# Mikrolysreklamen.net
KiCad netlist of a schematic drawn in Altium Designer
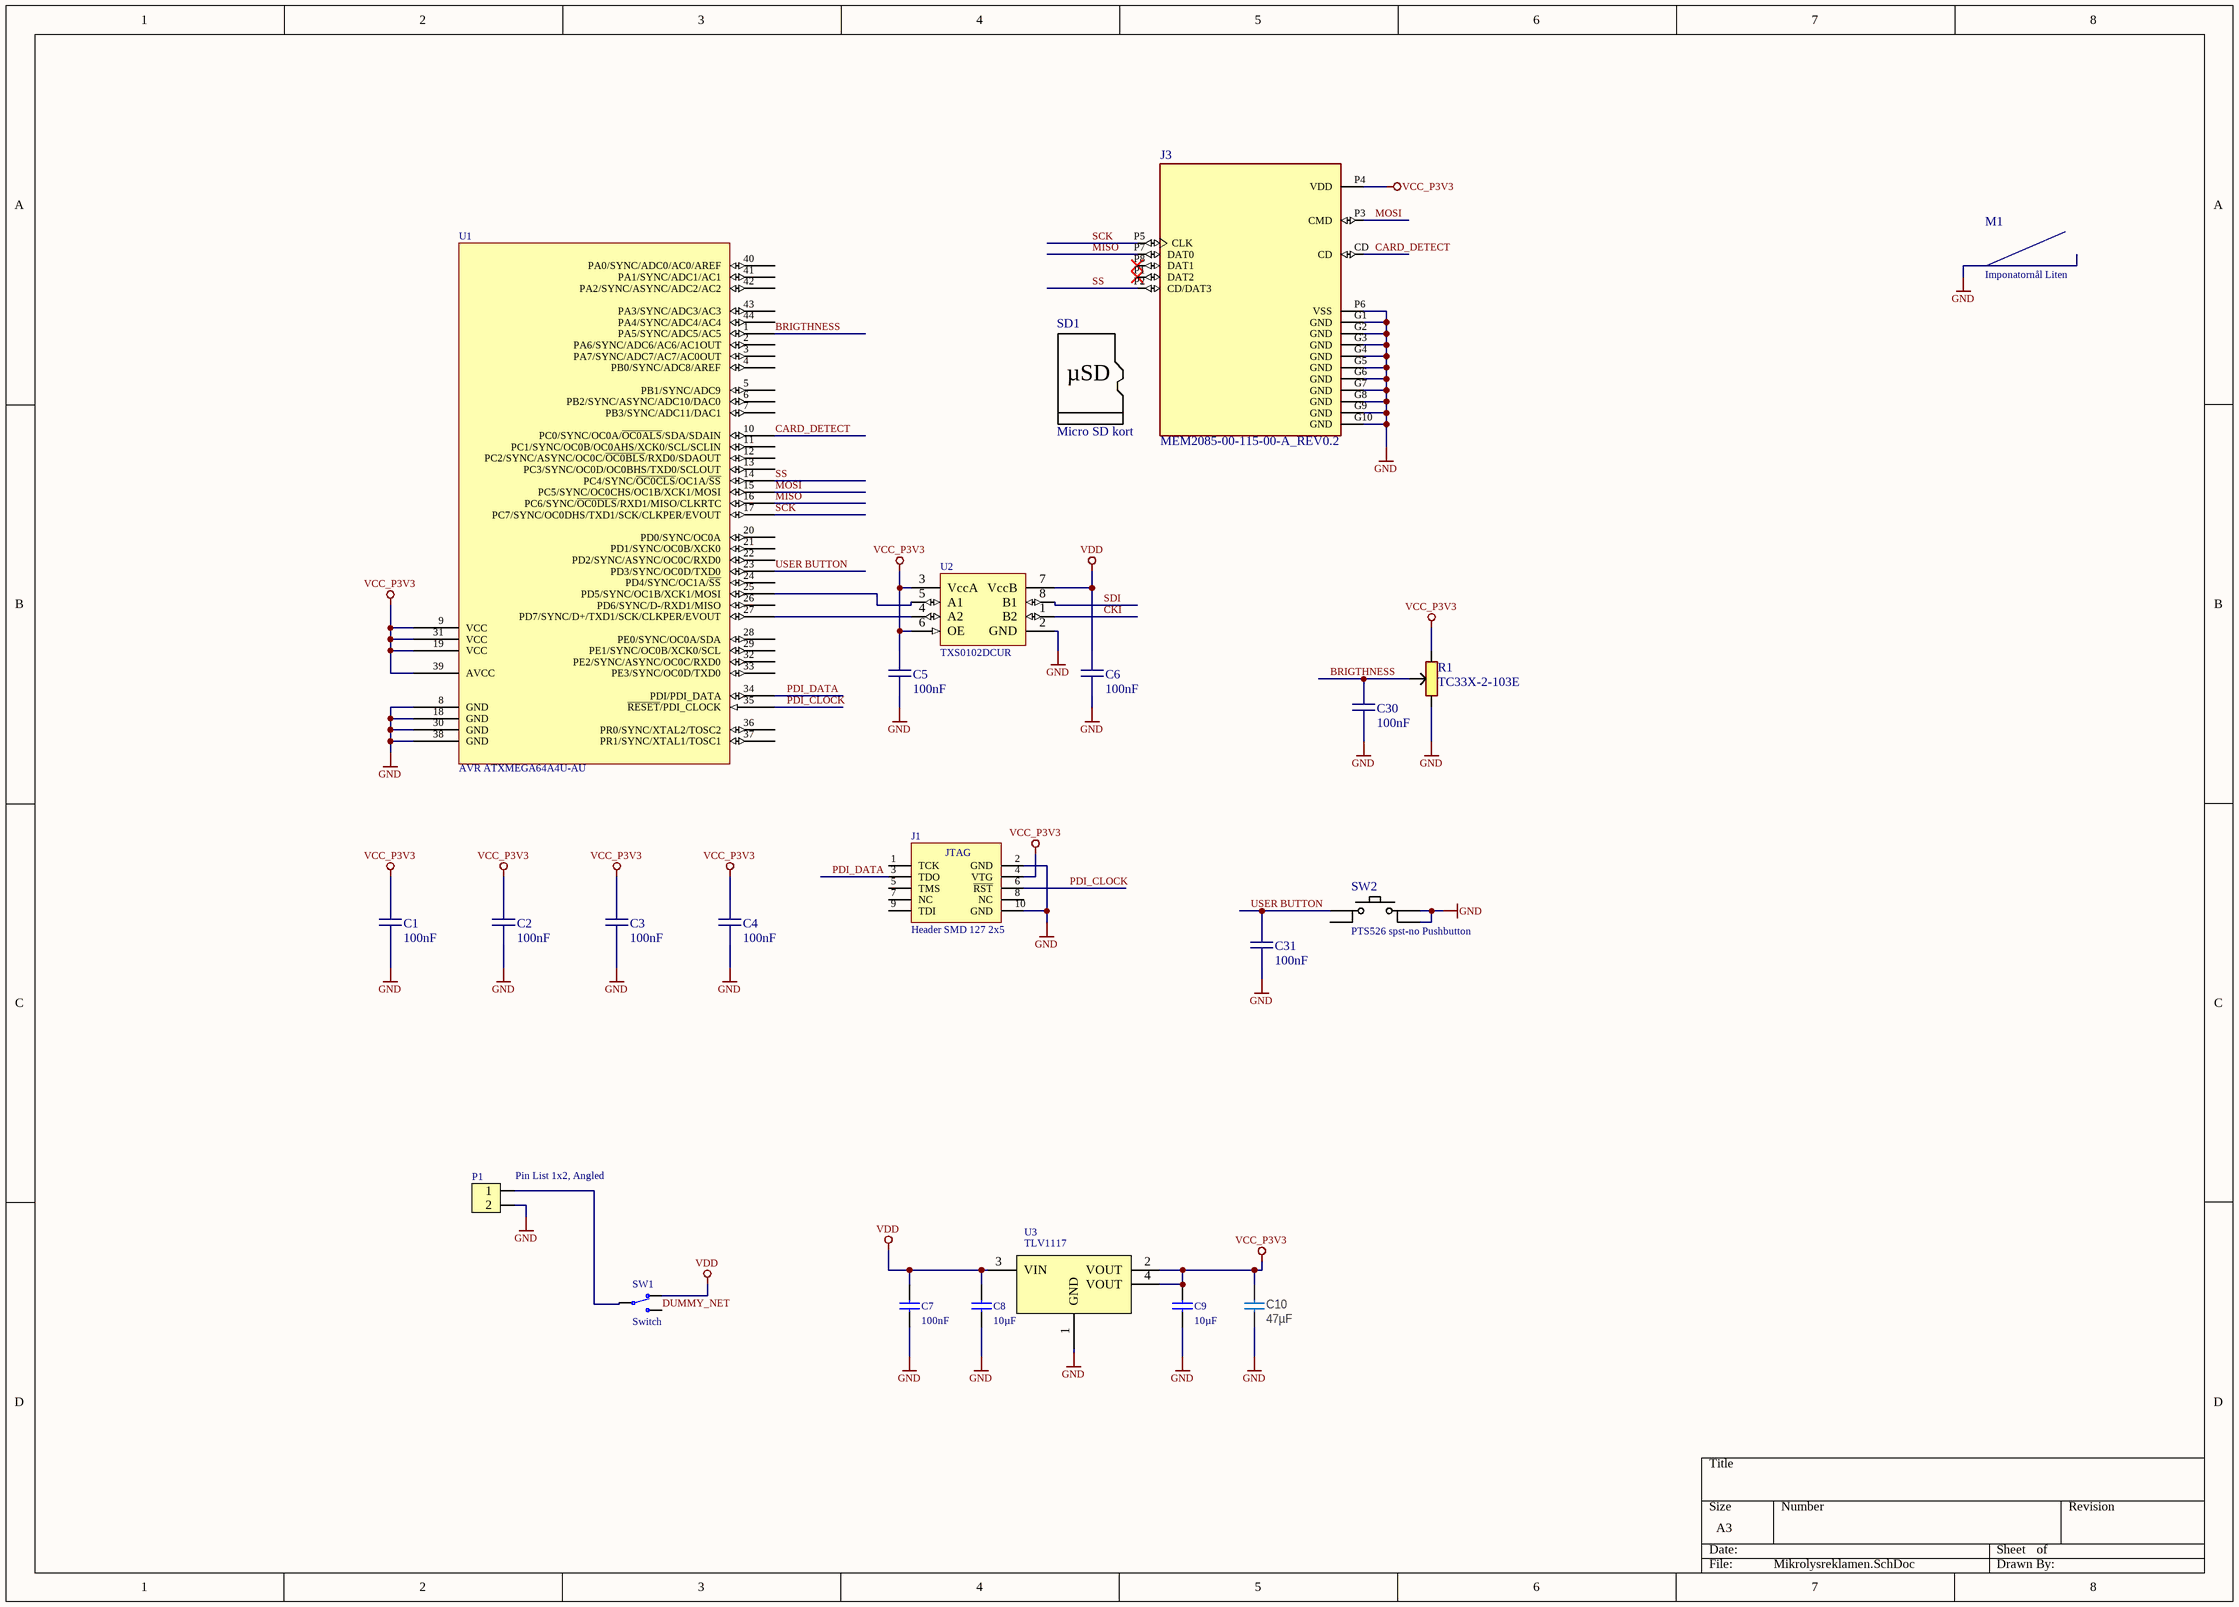
[diagram p0: Mikrolysreklamen.SchDoc]

(export (version "E")
  (design (tool "Eeschema 10.0.6"))
  (components
    (comp (ref "C1")
      (value "100nF")
      (footprint "CAPC0603(1608)55_N")
      (libsource (lib "OVLib_64") (part "CAP"))
    )
    (comp (ref "C2")
      (value "100nF")
      (footprint "CAPC0603(1608)55_N")
      (libsource (lib "OVLib_64") (part "CAP"))
    )
    (comp (ref "C3")
      (value "100nF")
      (footprint "CAPC0603(1608)55_N")
      (libsource (lib "OVLib_64") (part "CAP"))
    )
    (comp (ref "C4")
      (value "100nF")
      (footprint "CAPC0603(1608)55_N")
      (libsource (lib "OVLib_64") (part "CAP"))
    )
    (comp (ref "C5")
      (value "100nF")
      (footprint "CAPC0603(1608)55_N")
      (libsource (lib "OVLib_64") (part "CAP"))
    )
    (comp (ref "C6")
      (value "100nF")
      (footprint "CAPC0603(1608)55_N")
      (libsource (lib "OVLib_64") (part "CAP"))
    )
    (comp (ref "C7")
      (value "100nF")
      (footprint "CAPC1005X04L")
      (description "Capacitor, X7R, ±10%")
      (fields (field (name "PART NUMBER") "C0402-100n") (field (name "PUBLISHER") "Nordic Semiconductor"))
      (libsource (lib "Nordic Passive DB") (part "CAP"))
    )
    (comp (ref "C8")
      (value "10µF")
      (footprint "CAPC1608X06L")
      (description "Capacitor, X5R, ±20%")
      (fields (field (name "PART NUMBER") "C0603-10µ") (field (name "PUBLISHER") "Nordic Semiconductor"))
      (libsource (lib "Nordic Passive DB") (part "CAP"))
    )
    (comp (ref "C9")
      (value "10µF")
      (footprint "CAPC1608X06L")
      (description "Capacitor, X5R, ±20%")
      (fields (field (name "PART NUMBER") "C0603-10µ") (field (name "PUBLISHER") "Nordic Semiconductor"))
      (libsource (lib "Nordic Passive DB") (part "CAP"))
    )
    (comp (ref "C10")
      (value "47µF")
      (footprint "CAPC2012X11L")
      (description "Capacitor, X5R, ±20%, 6.3V")
      (fields
        (field (name "PART NUMBER") "C0805-47µ")
        (field (name "MANUFACTURER") "Taiyo Yuden")
        (field (name "PUBLISHER") "Nordic Semiconductor")
      )
      (libsource (lib "Nordic Passive DB") (part "CAP"))
    )
    (comp (ref "C30")
      (value "100nF")
      (footprint "CAPC0603(1608)55_N")
      (libsource (lib "OVLib_64") (part "CAP"))
    )
    (comp (ref "C31")
      (value "100nF")
      (footprint "CAPC0603(1608)55_N")
      (libsource (lib "OVLib_64") (part "CAP"))
    )
    (comp (ref "J1")
      (value "Header SMD 127 2x5")
      (footprint "SMDHDRV10P127_2X5_615X330X560B")
      (description "1,27mm Pitch SMD Header")
      (libsource (lib "OVLib") (part "AVRJTAG"))
    )
    (comp (ref "J3")
      (value "MEM2085-00-115-00-A_REV0.2")
      (footprint "GCT_MEM2085-00-115-00-A_REV0.2")
      (description "MicroSD Push pull Memory Card Connector")
      (fields (field (name "MP") "MEM2085-00-115-00-A") (field (name "MF") "Global Connector Technology"))
      (libsource (lib "OVLib_64") (part "MEM2085-00-115-00-A_REV0.2"))
    )
    (comp (ref "M1")
      (value "Imponatornål Liten")
      (footprint "Imponatornaal_liten")
      (libsource (lib "Imponatornaal") (part "Imponatornaal"))
    )
    (comp (ref "P1")
      (value "Pin List 1x2, Angled")
      (footprint "LIST_ANG_1x2-SMD-2.54MM")
      (description "Pin List 1x2, 2.54mm (100mil), Right Angled, SMD")
      (fields
        (field (name "PART NUMBER") "Pin List Ang 1x2 SMD, 2.54mm")
        (field (name "MANUFACTURER") "W-CON")
        (field (name "PUBLISHER") "Nordic Semiconductor")
      )
      (libsource (lib "Nordic Passive DB") (part "CONN-2"))
    )
    (comp (ref "R1")
      (value "TC33X-2-103E")
      (footprint "TRIM_TC33X-2-103E")
      (libsource (lib "OVLib_64") (part "Potmeter"))
    )
    (comp (ref "SD1")
      (value "Micro SD kort")
      (footprint "microsdcard")
      (libsource (lib "OVLib_64") (part "microsdcard"))
    )
    (comp (ref "SW1")
      (value "Switch")
      (footprint "JS102011SAQN")
      (description "SMD slide Switch (ON-ON)")
      (fields
        (field (name "PART NUMBER") "JS102011SAQN")
        (field (name "MANUFACTURER") "C&K Components")
        (field (name "PUBLISHER") "Nordic Semiconductor")
      )
      (libsource (lib "Nordic Discrete DB") (part "SW-SPDT"))
    )
    (comp (ref "SW2")
      (value "PTS526 spst-no Pushbutton")
      (footprint "PTS526_SK15_SMTR2_LFS")
      (libsource (lib "OVLib_64") (part "Pushbutton"))
    )
    (comp (ref "U1")
      (value "AVR ATXMEGA64A4U-AU")
      (footprint "TQFP80P1200X1200X120-44N")
      (description "Mikrokontroller")
      (libsource (lib "OVLib") (part "ATXMEGA-A4U"))
    )
    (comp (ref "U2")
      (value "TXS0102DCUR")
      (footprint "TSSOP50P310X90-8N")
      (description "IC VOLT-LEVEL TRANSLATOR 8-US8")
      (fields
        (field (name "MANUFACTURER") "Texas Instruments")
        (field (name "PUBLISHER") "Nordic Semiconductor")
      )
      (libsource (lib "Nordic Active DB") (part "TXS0102DC"))
    )
    (comp (ref "U3")
      (value "TLV1117")
      (footprint "SOT230P700X180-4N")
      (description "REG LDO 3.3V 0.8A SOT223")
      (fields
        (field (name "PART NUMBER") "TLV1117-33CDCYR")
        (field (name "MANUFACTURER") "Texas Instruments")
        (field (name "PUBLISHER") "Nordic Semiconductor")
      )
      (libsource (lib "Nordic Active DB") (part "LD1117_fixed"))
    )
  )
  (nets
    (net (code "1") (name "/BRIGTHNESS") (class "Default")
      (node (ref "C30") (pin "2") (pinfunction "2_2") (pintype "passive"))
      (node (ref "R1") (pin "2") (pinfunction "2_2") (pintype "passive"))
      (node (ref "U1") (pin "1") (pinfunction "PA5/SYNC/ADC5/AC5_1") (pintype "bidirectional"))
    )
    (net (code "2") (name "/CARD_DETECT") (class "Default")
      (node (ref "J3") (pin "CD") (pinfunction "CD_CD") (pintype "bidirectional"))
      (node (ref "U1") (pin "10") (pinfunction "PC0/SYNC/OC0A/~{OC0ALS}/SDA/SDAIN_10") (pintype "bidirectional"))
    )
    (net (code "3") (name "/CKI") (class "Default")
      (node (ref "U2") (pin "1") (pinfunction "B2_1") (pintype "bidirectional"))
    )
    (net (code "4") (name "/DUMMY_NET") (class "Default")
      (node (ref "SW1") (pin "3") (pinfunction "N.O_3") (pintype "passive"))
    )
    (net (code "5") (name "/MISO") (class "Default")
      (node (ref "J3") (pin "P7") (pinfunction "DAT0_P7") (pintype "bidirectional"))
      (node (ref "U1") (pin "16") (pinfunction "PC6/SYNC/~{OC0DLS}/RXD1/MISO/CLKRTC_16") (pintype "bidirectional"))
    )
    (net (code "6") (name "/MOSI") (class "Default")
      (node (ref "J3") (pin "P3") (pinfunction "CMD_P3") (pintype "bidirectional"))
      (node (ref "U1") (pin "15") (pinfunction "PC5/SYNC/OC0CHS/OC1B/XCK1/MOSI_15") (pintype "bidirectional"))
    )
    (net (code "7") (name "/PDI_CLOCK") (class "Default")
      (node (ref "J1") (pin "6") (pinfunction "~{RST}_6") (pintype "passive"))
      (node (ref "U1") (pin "35") (pinfunction "~{RESET}/PDI_CLOCK_35") (pintype "input"))
    )
    (net (code "8") (name "/PDI_DATA") (class "Default")
      (node (ref "J1") (pin "3") (pinfunction "TDO_3") (pintype "passive"))
      (node (ref "U1") (pin "34") (pinfunction "PDI/PDI_DATA_34") (pintype "bidirectional"))
    )
    (net (code "9") (name "/SCK") (class "Default")
      (node (ref "J3") (pin "P5") (pinfunction "CLK_P5") (pintype "bidirectional"))
      (node (ref "U1") (pin "17") (pinfunction "PC7/SYNC/OC0DHS/TXD1/SCK/CLKPER/EVOUT_17") (pintype "bidirectional"))
    )
    (net (code "10") (name "/SDI") (class "Default")
      (node (ref "U2") (pin "8") (pinfunction "B1_8") (pintype "bidirectional"))
    )
    (net (code "11") (name "/SS") (class "Default")
      (node (ref "J3") (pin "P2") (pinfunction "CD/DAT3_P2") (pintype "bidirectional"))
      (node (ref "U1") (pin "14") (pinfunction "PC4/SYNC/~{OC0CLS}/OC1A/~{SS}_14") (pintype "bidirectional"))
    )
    (net (code "12") (name "/USER BUTTON") (class "Default")
      (node (ref "C31") (pin "2") (pinfunction "2_2") (pintype "passive"))
      (node (ref "SW2") (pin "1") (pinfunction "1_1") (pintype "passive"))
      (node (ref "U1") (pin "23") (pinfunction "PD3/SYNC/OC0D/TXD0_23") (pintype "bidirectional"))
    )
    (net (code "13") (name "GND") (class "Default")
      (node (ref "C1") (pin "1") (pinfunction "1_1") (pintype "passive"))
      (node (ref "C10") (pin "1") (pinfunction "1_1") (pintype "passive"))
      (node (ref "C2") (pin "1") (pinfunction "1_1") (pintype "passive"))
      (node (ref "C3") (pin "1") (pinfunction "1_1") (pintype "passive"))
      (node (ref "C30") (pin "1") (pinfunction "1_1") (pintype "passive"))
      (node (ref "C31") (pin "1") (pinfunction "1_1") (pintype "passive"))
      (node (ref "C4") (pin "1") (pinfunction "1_1") (pintype "passive"))
      (node (ref "C5") (pin "1") (pinfunction "1_1") (pintype "passive"))
      (node (ref "C6") (pin "1") (pinfunction "1_1") (pintype "passive"))
      (node (ref "C7") (pin "1") (pinfunction "1_1") (pintype "passive"))
      (node (ref "C8") (pin "1") (pinfunction "1_1") (pintype "passive"))
      (node (ref "C9") (pin "1") (pinfunction "1_1") (pintype "passive"))
      (node (ref "J1") (pin "10") (pinfunction "GND_10") (pintype "passive"))
      (node (ref "J1") (pin "2") (pinfunction "GND_2") (pintype "passive"))
      (node (ref "J3") (pin "G1") (pinfunction "GND_G1") (pintype "power_in"))
      (node (ref "J3") (pin "G10") (pinfunction "GND_G10") (pintype "power_in"))
      (node (ref "J3") (pin "G2") (pinfunction "GND_G2") (pintype "power_in"))
      (node (ref "J3") (pin "G3") (pinfunction "GND_G3") (pintype "power_in"))
      (node (ref "J3") (pin "G4") (pinfunction "GND_G4") (pintype "power_in"))
      (node (ref "J3") (pin "G5") (pinfunction "GND_G5") (pintype "power_in"))
      (node (ref "J3") (pin "G6") (pinfunction "GND_G6") (pintype "power_in"))
      (node (ref "J3") (pin "G7") (pinfunction "GND_G7") (pintype "power_in"))
      (node (ref "J3") (pin "G8") (pinfunction "GND_G8") (pintype "power_in"))
      (node (ref "J3") (pin "G9") (pinfunction "GND_G9") (pintype "power_in"))
      (node (ref "J3") (pin "P6") (pinfunction "VSS_P6") (pintype "power_in"))
      (node (ref "M1") (pin "0") (pinfunction "0_0") (pintype "passive"))
      (node (ref "P1") (pin "2") (pinfunction "2_2") (pintype "passive"))
      (node (ref "R1") (pin "1") (pinfunction "1_1") (pintype "passive"))
      (node (ref "SW2") (pin "3") (pinfunction "3_3") (pintype "passive"))
      (node (ref "SW2") (pin "4") (pinfunction "4_4") (pintype "passive"))
      (node (ref "U1") (pin "18") (pinfunction "GND_18") (pintype "power_in"))
      (node (ref "U1") (pin "30") (pinfunction "GND_30") (pintype "power_in"))
      (node (ref "U1") (pin "38") (pinfunction "GND_38") (pintype "power_in"))
      (node (ref "U1") (pin "8") (pinfunction "GND_8") (pintype "power_in"))
      (node (ref "U2") (pin "2") (pinfunction "GND_2") (pintype "power_in"))
      (node (ref "U3") (pin "1") (pinfunction "GND_1") (pintype "power_in"))
    )
    (net (code "14") (name "Net-(SW1-COM)") (class "Default")
      (node (ref "P1") (pin "1") (pinfunction "1_1") (pintype "passive"))
      (node (ref "SW1") (pin "2") (pinfunction "COM_2") (pintype "passive"))
    )
    (net (code "15") (name "Net-(U1-PD5{slash}SYNC{slash}OC1B{slash}XCK1{slash}MOSI)") (class "Default")
      (node (ref "U1") (pin "25") (pinfunction "PD5/SYNC/OC1B/XCK1/MOSI_25") (pintype "bidirectional"))
      (node (ref "U2") (pin "5") (pinfunction "A1_5") (pintype "bidirectional"))
    )
    (net (code "16") (name "Net-(U1-PD7{slash}SYNC{slash}D+{slash}TXD1{slash}SCK{slash}CLKPER{slash}EVOUT)") (class "Default")
      (node (ref "U1") (pin "27") (pinfunction "PD7/SYNC/D+/TXD1/SCK/CLKPER/EVOUT_27") (pintype "bidirectional"))
      (node (ref "U2") (pin "4") (pinfunction "A2_4") (pintype "bidirectional"))
    )
    (net (code "17") (name "VCC_P3V3") (class "Default")
      (node (ref "C1") (pin "2") (pinfunction "2_2") (pintype "passive"))
      (node (ref "C10") (pin "2") (pinfunction "2_2") (pintype "passive"))
      (node (ref "C2") (pin "2") (pinfunction "2_2") (pintype "passive"))
      (node (ref "C3") (pin "2") (pinfunction "2_2") (pintype "passive"))
      (node (ref "C4") (pin "2") (pinfunction "2_2") (pintype "passive"))
      (node (ref "C5") (pin "2") (pinfunction "2_2") (pintype "passive"))
      (node (ref "C9") (pin "2") (pinfunction "2_2") (pintype "passive"))
      (node (ref "J1") (pin "4") (pinfunction "VTG_4") (pintype "passive"))
      (node (ref "J3") (pin "P4") (pinfunction "VDD_P4") (pintype "power_in"))
      (node (ref "R1") (pin "3") (pinfunction "3_3") (pintype "passive"))
      (node (ref "U1") (pin "19") (pinfunction "VCC_19") (pintype "power_in"))
      (node (ref "U1") (pin "31") (pinfunction "VCC_31") (pintype "power_in"))
      (node (ref "U1") (pin "39") (pinfunction "AVCC_39") (pintype "power_in"))
      (node (ref "U1") (pin "9") (pinfunction "VCC_9") (pintype "power_in"))
      (node (ref "U2") (pin "3") (pinfunction "VccA_3") (pintype "power_in"))
      (node (ref "U2") (pin "6") (pinfunction "OE_6") (pintype "input"))
      (node (ref "U3") (pin "2") (pinfunction "VOUT_2") (pintype "power_in"))
      (node (ref "U3") (pin "4") (pinfunction "VOUT_4") (pintype "power_in"))
    )
    (net (code "18") (name "VDD") (class "Default")
      (node (ref "C6") (pin "2") (pinfunction "2_2") (pintype "passive"))
      (node (ref "C7") (pin "2") (pinfunction "2_2") (pintype "passive"))
      (node (ref "C8") (pin "2") (pinfunction "2_2") (pintype "passive"))
      (node (ref "SW1") (pin "1") (pinfunction "N.C_1") (pintype "passive"))
      (node (ref "U2") (pin "7") (pinfunction "VccB_7") (pintype "power_in"))
      (node (ref "U3") (pin "3") (pinfunction "VIN_3") (pintype "power_in"))
    )
    (net (code "19") (name "unconnected-(J1-NC-Pad7)") (class "Default")
      (node (ref "J1") (pin "7") (pinfunction "NC_7") (pintype "passive"))
    )
    (net (code "20") (name "unconnected-(J1-NC-Pad8)") (class "Default")
      (node (ref "J1") (pin "8") (pinfunction "NC_8") (pintype "passive"))
    )
    (net (code "21") (name "unconnected-(J1-TCK-Pad1)") (class "Default")
      (node (ref "J1") (pin "1") (pinfunction "TCK_1") (pintype "passive"))
    )
    (net (code "22") (name "unconnected-(J1-TDI-Pad9)") (class "Default")
      (node (ref "J1") (pin "9") (pinfunction "TDI_9") (pintype "passive"))
    )
    (net (code "23") (name "unconnected-(J1-TMS-Pad5)") (class "Default")
      (node (ref "J1") (pin "5") (pinfunction "TMS_5") (pintype "passive"))
    )
    (net (code "24") (name "unconnected-(J3-DAT1-PadP8)") (class "Default")
      (node (ref "J3") (pin "P8") (pinfunction "DAT1_P8") (pintype "bidirectional+no_connect"))
    )
    (net (code "25") (name "unconnected-(J3-DAT2-PadP1)") (class "Default")
      (node (ref "J3") (pin "P1") (pinfunction "DAT2_P1") (pintype "bidirectional+no_connect"))
    )
    (net (code "26") (name "unconnected-(SW2-Pad2)") (class "Default")
      (node (ref "SW2") (pin "2") (pinfunction "2_2") (pintype "passive"))
    )
    (net (code "27") (name "unconnected-(U1-PA0{slash}SYNC{slash}ADC0{slash}AC0{slash}AREF-Pad40)") (class "Default")
      (node (ref "U1") (pin "40") (pinfunction "PA0/SYNC/ADC0/AC0/AREF_40") (pintype "bidirectional"))
    )
    (net (code "28") (name "unconnected-(U1-PA1{slash}SYNC{slash}ADC1{slash}AC1-Pad41)") (class "Default")
      (node (ref "U1") (pin "41") (pinfunction "PA1/SYNC/ADC1/AC1_41") (pintype "bidirectional"))
    )
    (net (code "29") (name "unconnected-(U1-PA2{slash}SYNC{slash}ASYNC{slash}ADC2{slash}AC2-Pad42)") (class "Default")
      (node (ref "U1") (pin "42") (pinfunction "PA2/SYNC/ASYNC/ADC2/AC2_42") (pintype "bidirectional"))
    )
    (net (code "30") (name "unconnected-(U1-PA3{slash}SYNC{slash}ADC3{slash}AC3-Pad43)") (class "Default")
      (node (ref "U1") (pin "43") (pinfunction "PA3/SYNC/ADC3/AC3_43") (pintype "bidirectional"))
    )
    (net (code "31") (name "unconnected-(U1-PA4{slash}SYNC{slash}ADC4{slash}AC4-Pad44)") (class "Default")
      (node (ref "U1") (pin "44") (pinfunction "PA4/SYNC/ADC4/AC4_44") (pintype "bidirectional"))
    )
    (net (code "32") (name "unconnected-(U1-PA6{slash}SYNC{slash}ADC6{slash}AC6{slash}AC1OUT-Pad2)") (class "Default")
      (node (ref "U1") (pin "2") (pinfunction "PA6/SYNC/ADC6/AC6/AC1OUT_2") (pintype "bidirectional"))
    )
    (net (code "33") (name "unconnected-(U1-PA7{slash}SYNC{slash}ADC7{slash}AC7{slash}AC0OUT-Pad3)") (class "Default")
      (node (ref "U1") (pin "3") (pinfunction "PA7/SYNC/ADC7/AC7/AC0OUT_3") (pintype "bidirectional"))
    )
    (net (code "34") (name "unconnected-(U1-PB0{slash}SYNC{slash}ADC8{slash}AREF-Pad4)") (class "Default")
      (node (ref "U1") (pin "4") (pinfunction "PB0/SYNC/ADC8/AREF_4") (pintype "bidirectional"))
    )
    (net (code "35") (name "unconnected-(U1-PB1{slash}SYNC{slash}ADC9-Pad5)") (class "Default")
      (node (ref "U1") (pin "5") (pinfunction "PB1/SYNC/ADC9_5") (pintype "bidirectional"))
    )
    (net (code "36") (name "unconnected-(U1-PB2{slash}SYNC{slash}ASYNC{slash}ADC10{slash}DAC0-Pad6)") (class "Default")
      (node (ref "U1") (pin "6") (pinfunction "PB2/SYNC/ASYNC/ADC10/DAC0_6") (pintype "bidirectional"))
    )
    (net (code "37") (name "unconnected-(U1-PB3{slash}SYNC{slash}ADC11{slash}DAC1-Pad7)") (class "Default")
      (node (ref "U1") (pin "7") (pinfunction "PB3/SYNC/ADC11/DAC1_7") (pintype "bidirectional"))
    )
    (net (code "38") (name "unconnected-(U1-PC1{slash}SYNC{slash}OC0B{slash}OC0AHS{slash}XCK0{slash}SCL{slash}SCLIN-Pad11)") (class "Default")
      (node (ref "U1") (pin "11") (pinfunction "PC1/SYNC/OC0B/OC0AHS/XCK0/SCL/SCLIN_11") (pintype "bidirectional"))
    )
    (net (code "39") (name "unconnected-(U1-PC2{slash}SYNC{slash}ASYNC{slash}OC0C{slash}~{OC0BLS}{slash}RXD0{slash}SDAOUT-Pad12)") (class "Default")
      (node (ref "U1") (pin "12") (pinfunction "PC2/SYNC/ASYNC/OC0C/~{OC0BLS}/RXD0/SDAOUT_12") (pintype "bidirectional"))
    )
    (net (code "40") (name "unconnected-(U1-PC3{slash}SYNC{slash}OC0D{slash}OC0BHS{slash}TXD0{slash}SCLOUT-Pad13)") (class "Default")
      (node (ref "U1") (pin "13") (pinfunction "PC3/SYNC/OC0D/OC0BHS/TXD0/SCLOUT_13") (pintype "bidirectional"))
    )
    (net (code "41") (name "unconnected-(U1-PD0{slash}SYNC{slash}OC0A-Pad20)") (class "Default")
      (node (ref "U1") (pin "20") (pinfunction "PD0/SYNC/OC0A_20") (pintype "bidirectional"))
    )
    (net (code "42") (name "unconnected-(U1-PD1{slash}SYNC{slash}OC0B{slash}XCK0-Pad21)") (class "Default")
      (node (ref "U1") (pin "21") (pinfunction "PD1/SYNC/OC0B/XCK0_21") (pintype "bidirectional"))
    )
    (net (code "43") (name "unconnected-(U1-PD2{slash}SYNC{slash}ASYNC{slash}OC0C{slash}RXD0-Pad22)") (class "Default")
      (node (ref "U1") (pin "22") (pinfunction "PD2/SYNC/ASYNC/OC0C/RXD0_22") (pintype "bidirectional"))
    )
    (net (code "44") (name "unconnected-(U1-PD4{slash}SYNC{slash}OC1A{slash}~{SS}-Pad24)") (class "Default")
      (node (ref "U1") (pin "24") (pinfunction "PD4/SYNC/OC1A/~{SS}_24") (pintype "bidirectional"))
    )
    (net (code "45") (name "unconnected-(U1-PD6{slash}SYNC{slash}D-{slash}RXD1{slash}MISO-Pad26)") (class "Default")
      (node (ref "U1") (pin "26") (pinfunction "PD6/SYNC/D-/RXD1/MISO_26") (pintype "bidirectional"))
    )
    (net (code "46") (name "unconnected-(U1-PE0{slash}SYNC{slash}OC0A{slash}SDA-Pad28)") (class "Default")
      (node (ref "U1") (pin "28") (pinfunction "PE0/SYNC/OC0A/SDA_28") (pintype "bidirectional"))
    )
    (net (code "47") (name "unconnected-(U1-PE1{slash}SYNC{slash}OC0B{slash}XCK0{slash}SCL-Pad29)") (class "Default")
      (node (ref "U1") (pin "29") (pinfunction "PE1/SYNC/OC0B/XCK0/SCL_29") (pintype "bidirectional"))
    )
    (net (code "48") (name "unconnected-(U1-PE2{slash}SYNC{slash}ASYNC{slash}OC0C{slash}RXD0-Pad32)") (class "Default")
      (node (ref "U1") (pin "32") (pinfunction "PE2/SYNC/ASYNC/OC0C/RXD0_32") (pintype "bidirectional"))
    )
    (net (code "49") (name "unconnected-(U1-PE3{slash}SYNC{slash}OC0D{slash}TXD0-Pad33)") (class "Default")
      (node (ref "U1") (pin "33") (pinfunction "PE3/SYNC/OC0D/TXD0_33") (pintype "bidirectional"))
    )
    (net (code "50") (name "unconnected-(U1-PR0{slash}SYNC{slash}XTAL2{slash}TOSC2-Pad36)") (class "Default")
      (node (ref "U1") (pin "36") (pinfunction "PR0/SYNC/XTAL2/TOSC2_36") (pintype "bidirectional"))
    )
    (net (code "51") (name "unconnected-(U1-PR1{slash}SYNC{slash}XTAL1{slash}TOSC1-Pad37)") (class "Default")
      (node (ref "U1") (pin "37") (pinfunction "PR1/SYNC/XTAL1/TOSC1_37") (pintype "bidirectional"))
    )
  )
)
